# driverPZT_01.net
KiCad netlist of a schematic drawn in EAGLE
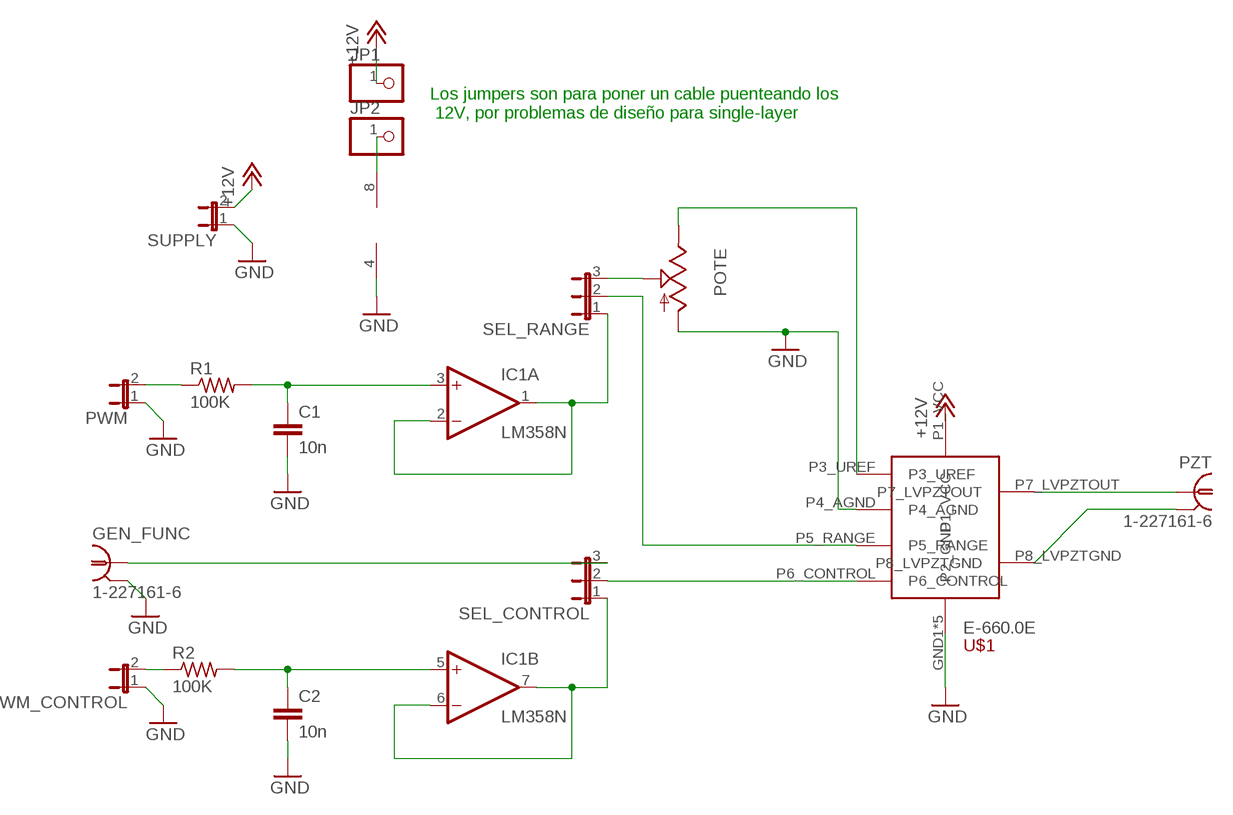
[diagram p0: schematic, sheet 1]

(export (version "E")
  (design (tool "Eeschema 10.0.6"))
  (components
    (comp (ref "C1")
      (value "10n")
      (footprint "eagle-import:C050-075X075")
      (libsource (lib "eagle-import") (part "C-EU050-075X075"))
    )
    (comp (ref "C2")
      (value "10n")
      (footprint "eagle-import:C050-075X075")
      (libsource (lib "eagle-import") (part "C-EU050-075X075"))
    )
    (comp (ref "GEN_FUNC")
      (value "1-227161-6")
      (footprint "eagle-import:AMP_227161")
      (fields (field (name "MF") "TYCO ELECTRONICS"))
      (libsource (lib "eagle-import") (part "?2271611--6"))
    )
    (comp (ref "IC1")
      (value "LM358N")
      (footprint "eagle-import:DIL08")
      (libsource (lib "eagle-import") (part "LM358N"))
    )
    (comp (ref "JP1")
      (value "PINHD-1X1")
      (footprint "eagle-import:1X01")
      (libsource (lib "eagle-import") (part "PINHD-1X1"))
    )
    (comp (ref "JP2")
      (value "PINHD-1X1")
      (footprint "eagle-import:1X01")
      (libsource (lib "eagle-import") (part "PINHD-1X1"))
    )
    (comp (ref "POTE")
      (value "TRIM_US-B64Y")
      (footprint "eagle-import:B64Y")
      (libsource (lib "eagle-import") (part "TRIM_US-B64Y"))
    )
    (comp (ref "PWM")
      (value "JP1E")
      (footprint "eagle-import:JP1")
      (libsource (lib "eagle-import") (part "JP1E"))
    )
    (comp (ref "PWM_CONTROL")
      (value "JP1E")
      (footprint "eagle-import:JP1")
      (libsource (lib "eagle-import") (part "JP1E"))
    )
    (comp (ref "PZT")
      (value "1-227161-6")
      (footprint "eagle-import:AMP_227161")
      (fields (field (name "MF") "TYCO ELECTRONICS"))
      (libsource (lib "eagle-import") (part "?2271611--6"))
    )
    (comp (ref "R1")
      (value "100K")
      (footprint "eagle-import:0207_12")
      (libsource (lib "eagle-import") (part "R-US_0207/12"))
    )
    (comp (ref "R2")
      (value "100K")
      (footprint "eagle-import:0207_12")
      (libsource (lib "eagle-import") (part "R-US_0207/12"))
    )
    (comp (ref "SEL_CONTROL")
      (value "JP2E")
      (footprint "eagle-import:JP2")
      (libsource (lib "eagle-import") (part "JP2E"))
    )
    (comp (ref "SEL_RANGE")
      (value "JP2E")
      (footprint "eagle-import:JP2")
      (libsource (lib "eagle-import") (part "JP2E"))
    )
    (comp (ref "SUPPLY")
      (value "JP1E")
      (footprint "eagle-import:JP1")
      (libsource (lib "eagle-import") (part "JP1E"))
    )
    (comp (ref "U$1")
      (value "E-660.0E")
      (footprint "eagle-import:E-660.0E")
      (libsource (lib "eagle-import") (part "E-660.0E"))
    )
  )
  (nets
    (net (code "1") (name "+12V") (class "Default")
      (node (ref "JP1") (pin "1") (pinfunction "1_1") (pintype "passive"))
      (node (ref "SUPPLY") (pin "2") (pinfunction "2_2") (pintype "passive"))
      (node (ref "U$1") (pin "P1_VCC") (pinfunction "P1_VCC_P1_VCC") (pintype "bidirectional"))
    )
    (net (code "2") (name "GND") (class "Default")
      (node (ref "C1") (pin "2") (pinfunction "2_2") (pintype "passive"))
      (node (ref "C2") (pin "2") (pinfunction "2_2") (pintype "passive"))
      (node (ref "GEN_FUNC") (pin "2") (pinfunction "2_2") (pintype "passive"))
      (node (ref "IC1") (pin "4") (pinfunction "V-_4") (pintype "power_in"))
      (node (ref "POTE") (pin "A") (pinfunction "A_A") (pintype "passive"))
      (node (ref "PWM") (pin "1") (pinfunction "1_1") (pintype "passive"))
      (node (ref "PWM_CONTROL") (pin "1") (pinfunction "1_1") (pintype "passive"))
      (node (ref "SUPPLY") (pin "1") (pinfunction "1_1") (pintype "passive"))
      (node (ref "U$1") (pin "GND1") (pinfunction "P2_GND_GND1") (pintype "bidirectional"))
      (node (ref "U$1") (pin "GND2") (pinfunction "P2_GND_GND2") (pintype "bidirectional"))
      (node (ref "U$1") (pin "GND3") (pinfunction "P2_GND_GND3") (pintype "bidirectional"))
      (node (ref "U$1") (pin "GND4") (pinfunction "P2_GND_GND4") (pintype "bidirectional"))
      (node (ref "U$1") (pin "P2_GND") (pinfunction "P2_GND_P2_GND") (pintype "bidirectional"))
      (node (ref "U$1") (pin "P4_AGND") (pinfunction "P4_AGND_P4_AGND") (pintype "bidirectional"))
    )
    (net (code "3") (name "Net-(GEN_FUNC-Pad1)") (class "Default")
      (node (ref "GEN_FUNC") (pin "1") (pinfunction "1_1") (pintype "passive"))
      (node (ref "SEL_CONTROL") (pin "3") (pinfunction "3_3") (pintype "passive"))
    )
    (net (code "4") (name "Net-(IC1A-+IN)") (class "Default")
      (node (ref "C1") (pin "1") (pinfunction "1_1") (pintype "passive"))
      (node (ref "IC1") (pin "3") (pinfunction "+IN_3") (pintype "input"))
      (node (ref "R1") (pin "2") (pinfunction "2_2") (pintype "passive"))
    )
    (net (code "5") (name "Net-(IC1A--IN)") (class "Default")
      (node (ref "IC1") (pin "1") (pinfunction "OUT_1") (pintype "output"))
      (node (ref "IC1") (pin "2") (pinfunction "-IN_2") (pintype "input"))
      (node (ref "SEL_RANGE") (pin "1") (pinfunction "1_1") (pintype "passive"))
    )
    (net (code "6") (name "Net-(IC1B-+IN)") (class "Default")
      (node (ref "C2") (pin "1") (pinfunction "1_1") (pintype "passive"))
      (node (ref "IC1") (pin "5") (pinfunction "+IN_5") (pintype "input"))
      (node (ref "R2") (pin "2") (pinfunction "2_2") (pintype "passive"))
    )
    (net (code "7") (name "Net-(IC1B--IN)") (class "Default")
      (node (ref "IC1") (pin "6") (pinfunction "-IN_6") (pintype "input"))
      (node (ref "IC1") (pin "7") (pinfunction "OUT_7") (pintype "output"))
      (node (ref "SEL_CONTROL") (pin "1") (pinfunction "1_1") (pintype "passive"))
    )
    (net (code "8") (name "Net-(IC1C-V+)") (class "Default")
      (node (ref "IC1") (pin "8") (pinfunction "V+_8") (pintype "power_in"))
      (node (ref "JP2") (pin "1") (pinfunction "1_1") (pintype "passive"))
    )
    (net (code "9") (name "Net-(POTE-PadE)") (class "Default")
      (node (ref "POTE") (pin "E") (pinfunction "E_E") (pintype "passive"))
      (node (ref "U$1") (pin "P3_UREF") (pinfunction "P3_UREF_P3_UREF") (pintype "bidirectional"))
    )
    (net (code "10") (name "Net-(POTE-PadS)") (class "Default")
      (node (ref "POTE") (pin "S") (pinfunction "S_S") (pintype "passive"))
      (node (ref "SEL_RANGE") (pin "3") (pinfunction "3_3") (pintype "passive"))
    )
    (net (code "11") (name "Net-(PWM-Pad2)") (class "Default")
      (node (ref "PWM") (pin "2") (pinfunction "2_2") (pintype "passive"))
      (node (ref "R1") (pin "1") (pinfunction "1_1") (pintype "passive"))
    )
    (net (code "12") (name "Net-(PWM_CONTROL-Pad2)") (class "Default")
      (node (ref "PWM_CONTROL") (pin "2") (pinfunction "2_2") (pintype "passive"))
      (node (ref "R2") (pin "1") (pinfunction "1_1") (pintype "passive"))
    )
    (net (code "13") (name "Net-(PZT-Pad1)") (class "Default")
      (node (ref "PZT") (pin "1") (pinfunction "1_1") (pintype "passive"))
      (node (ref "U$1") (pin "P7_LVPZTOUT") (pinfunction "P7_LVPZTOUT_P7_LVPZTOUT") (pintype "bidirectional"))
    )
    (net (code "14") (name "Net-(PZT-Pad2)") (class "Default")
      (node (ref "PZT") (pin "2") (pinfunction "2_2") (pintype "passive"))
      (node (ref "U$1") (pin "P8_LVPZTGND") (pinfunction "P8_LVPZTGND_P8_LVPZTGND") (pintype "bidirectional"))
    )
    (net (code "15") (name "Net-(SEL_CONTROL-Pad2)") (class "Default")
      (node (ref "SEL_CONTROL") (pin "2") (pinfunction "2_2") (pintype "passive"))
      (node (ref "U$1") (pin "P6_CONTROL") (pinfunction "P6_CONTROL_P6_CONTROL") (pintype "bidirectional"))
    )
    (net (code "16") (name "Net-(SEL_RANGE-Pad2)") (class "Default")
      (node (ref "SEL_RANGE") (pin "2") (pinfunction "2_2") (pintype "passive"))
      (node (ref "U$1") (pin "P5_RANGE") (pinfunction "P5_RANGE_P5_RANGE") (pintype "bidirectional"))
    )
  )
)
